# mux-board.net
KiCad netlist of a schematic drawn in EAGLE
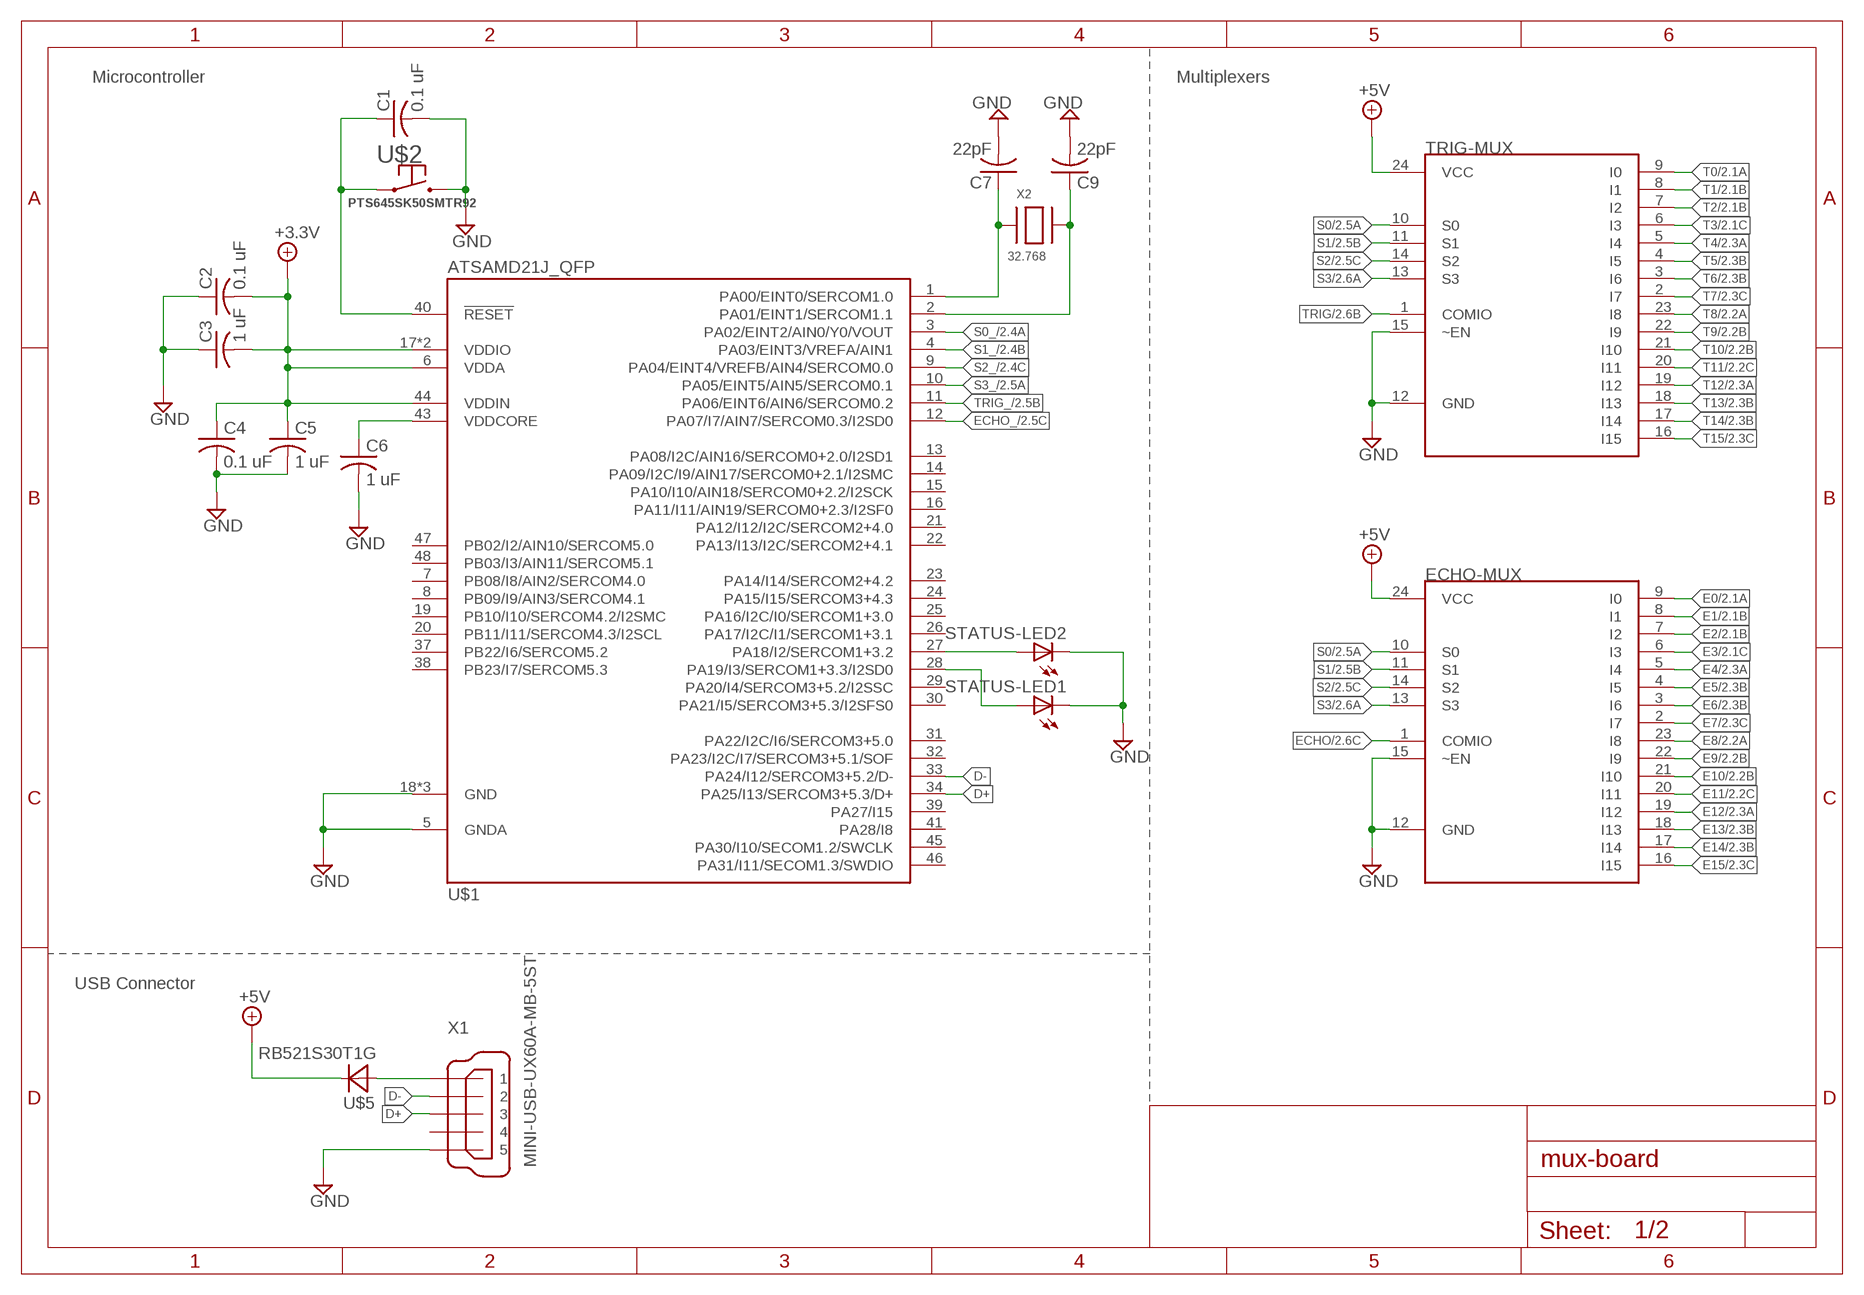
[diagram p0: schematic, sheet 1]
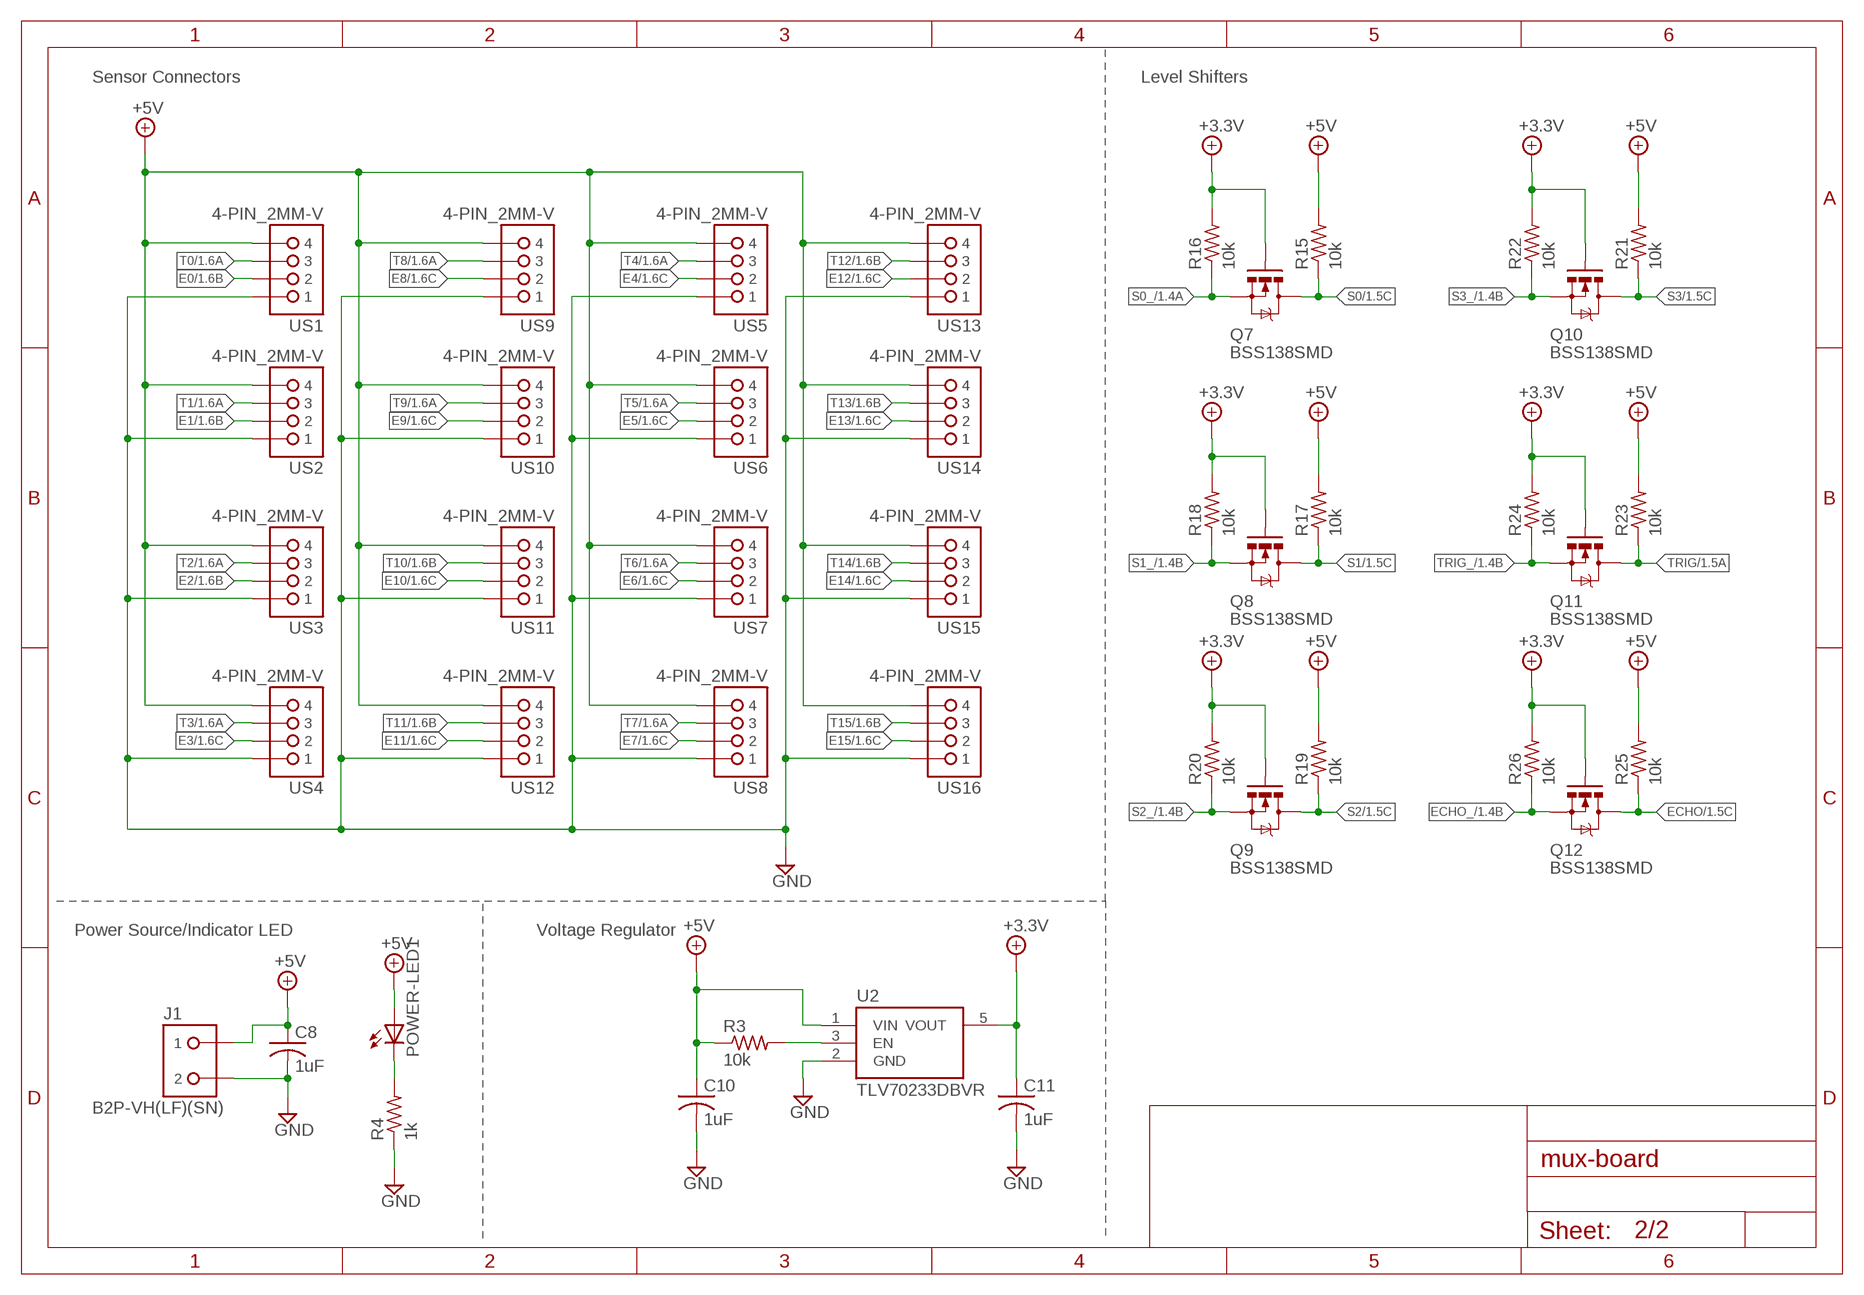
[diagram p1: schematic, sheet 2]

(export (version "E")
  (design (tool "Eeschema 10.0.6"))
  (components
    (comp (ref "C8")
      (value "1uF")
      (footprint "eagle-import:C0603")
      (libsource (lib "eagle-import") (part "C-USC0603"))
    )
    (comp (ref "C10")
      (value "1uF")
      (footprint "eagle-import:C0603")
      (libsource (lib "eagle-import") (part "C-USC0603"))
    )
    (comp (ref "C11")
      (value "1uF")
      (footprint "eagle-import:C0603")
      (libsource (lib "eagle-import") (part "C-USC0603"))
    )
    (comp (ref "J1")
      (value "B2P-VH(LF)(SN)")
      (footprint "eagle-import:B2P")
      (libsource (lib "eagle-import") (part "B2P?-VH(LF)(SN)"))
    )
    (comp (ref "POWER-LED1")
      (value "LEDSML0603")
      (footprint "eagle-import:SML0603")
      (libsource (lib "eagle-import") (part "LEDSML0603"))
    )
    (comp (ref "Q7")
      (value "BSS138SMD")
      (footprint "eagle-import:SPARKFUN_SOT23-3")
      (libsource (lib "eagle-import") (part "BSS138SMD"))
    )
    (comp (ref "Q8")
      (value "BSS138SMD")
      (footprint "eagle-import:SPARKFUN_SOT23-3")
      (libsource (lib "eagle-import") (part "BSS138SMD"))
    )
    (comp (ref "Q9")
      (value "BSS138SMD")
      (footprint "eagle-import:SPARKFUN_SOT23-3")
      (libsource (lib "eagle-import") (part "BSS138SMD"))
    )
    (comp (ref "Q10")
      (value "BSS138SMD")
      (footprint "eagle-import:SPARKFUN_SOT23-3")
      (libsource (lib "eagle-import") (part "BSS138SMD"))
    )
    (comp (ref "Q11")
      (value "BSS138SMD")
      (footprint "eagle-import:SPARKFUN_SOT23-3")
      (libsource (lib "eagle-import") (part "BSS138SMD"))
    )
    (comp (ref "Q12")
      (value "BSS138SMD")
      (footprint "eagle-import:SPARKFUN_SOT23-3")
      (libsource (lib "eagle-import") (part "BSS138SMD"))
    )
    (comp (ref "R3")
      (value "10k")
      (footprint "eagle-import:R0603")
      (libsource (lib "eagle-import") (part "resistor_348_R-US_R0603"))
    )
    (comp (ref "R4")
      (value "1k")
      (footprint "eagle-import:R0603")
      (libsource (lib "eagle-import") (part "resistor_348_R-US_R0603"))
    )
    (comp (ref "R15")
      (value "10k")
      (footprint "eagle-import:R0603")
      (libsource (lib "eagle-import") (part "R-US_R0603"))
    )
    (comp (ref "R16")
      (value "10k")
      (footprint "eagle-import:R0603")
      (libsource (lib "eagle-import") (part "R-US_R0603"))
    )
    (comp (ref "R17")
      (value "10k")
      (footprint "eagle-import:R0603")
      (libsource (lib "eagle-import") (part "R-US_R0603"))
    )
    (comp (ref "R18")
      (value "10k")
      (footprint "eagle-import:R0603")
      (libsource (lib "eagle-import") (part "R-US_R0603"))
    )
    (comp (ref "R19")
      (value "10k")
      (footprint "eagle-import:R0603")
      (libsource (lib "eagle-import") (part "R-US_R0603"))
    )
    (comp (ref "R20")
      (value "10k")
      (footprint "eagle-import:R0603")
      (libsource (lib "eagle-import") (part "R-US_R0603"))
    )
    (comp (ref "R21")
      (value "10k")
      (footprint "eagle-import:R0603")
      (libsource (lib "eagle-import") (part "R-US_R0603"))
    )
    (comp (ref "R22")
      (value "10k")
      (footprint "eagle-import:R0603")
      (libsource (lib "eagle-import") (part "R-US_R0603"))
    )
    (comp (ref "R23")
      (value "10k")
      (footprint "eagle-import:R0603")
      (libsource (lib "eagle-import") (part "R-US_R0603"))
    )
    (comp (ref "R24")
      (value "10k")
      (footprint "eagle-import:R0603")
      (libsource (lib "eagle-import") (part "R-US_R0603"))
    )
    (comp (ref "R25")
      (value "10k")
      (footprint "eagle-import:R0603")
      (libsource (lib "eagle-import") (part "R-US_R0603"))
    )
    (comp (ref "R26")
      (value "10k")
      (footprint "eagle-import:R0603")
      (libsource (lib "eagle-import") (part "R-US_R0603"))
    )
    (comp (ref "U2")
      (value "TLV70233DBVR")
      (footprint "eagle-import:SOT-23-5")
      (libsource (lib "eagle-import") (part "TLV70233DBVR"))
    )
    (comp (ref "US1")
      (value "4-PIN_2MM-V")
      (footprint "eagle-import:2MM-4-V")
      (libsource (lib "eagle-import") (part "4-PIN_2MM-V"))
    )
    (comp (ref "US2")
      (value "4-PIN_2MM-V")
      (footprint "eagle-import:2MM-4-V")
      (libsource (lib "eagle-import") (part "4-PIN_2MM-V"))
    )
    (comp (ref "US3")
      (value "4-PIN_2MM-V")
      (footprint "eagle-import:2MM-4-V")
      (libsource (lib "eagle-import") (part "4-PIN_2MM-V"))
    )
    (comp (ref "US4")
      (value "4-PIN_2MM-V")
      (footprint "eagle-import:2MM-4-V")
      (libsource (lib "eagle-import") (part "4-PIN_2MM-V"))
    )
    (comp (ref "US5")
      (value "4-PIN_2MM-V")
      (footprint "eagle-import:2MM-4-V")
      (libsource (lib "eagle-import") (part "4-PIN_2MM-V"))
    )
    (comp (ref "US6")
      (value "4-PIN_2MM-V")
      (footprint "eagle-import:2MM-4-V")
      (libsource (lib "eagle-import") (part "4-PIN_2MM-V"))
    )
    (comp (ref "US7")
      (value "4-PIN_2MM-V")
      (footprint "eagle-import:2MM-4-V")
      (libsource (lib "eagle-import") (part "4-PIN_2MM-V"))
    )
    (comp (ref "US8")
      (value "4-PIN_2MM-V")
      (footprint "eagle-import:2MM-4-V")
      (libsource (lib "eagle-import") (part "4-PIN_2MM-V"))
    )
    (comp (ref "US9")
      (value "4-PIN_2MM-V")
      (footprint "eagle-import:2MM-4-V")
      (libsource (lib "eagle-import") (part "4-PIN_2MM-V"))
    )
    (comp (ref "US10")
      (value "4-PIN_2MM-V")
      (footprint "eagle-import:2MM-4-V")
      (libsource (lib "eagle-import") (part "4-PIN_2MM-V"))
    )
    (comp (ref "US11")
      (value "4-PIN_2MM-V")
      (footprint "eagle-import:2MM-4-V")
      (libsource (lib "eagle-import") (part "4-PIN_2MM-V"))
    )
    (comp (ref "US12")
      (value "4-PIN_2MM-V")
      (footprint "eagle-import:2MM-4-V")
      (libsource (lib "eagle-import") (part "4-PIN_2MM-V"))
    )
    (comp (ref "US13")
      (value "4-PIN_2MM-V")
      (footprint "eagle-import:2MM-4-V")
      (libsource (lib "eagle-import") (part "4-PIN_2MM-V"))
    )
    (comp (ref "US14")
      (value "4-PIN_2MM-V")
      (footprint "eagle-import:2MM-4-V")
      (libsource (lib "eagle-import") (part "4-PIN_2MM-V"))
    )
    (comp (ref "US15")
      (value "4-PIN_2MM-V")
      (footprint "eagle-import:2MM-4-V")
      (libsource (lib "eagle-import") (part "4-PIN_2MM-V"))
    )
    (comp (ref "US16")
      (value "4-PIN_2MM-V")
      (footprint "eagle-import:2MM-4-V")
      (libsource (lib "eagle-import") (part "4-PIN_2MM-V"))
    )
    (comp (ref "C1")
      (value "0.1 uF")
      (footprint "eagle-import:C0603")
      (libsource (lib "eagle-import") (part "resistor_348_C-USC0603"))
    )
    (comp (ref "C2")
      (value "0.1 uF")
      (footprint "eagle-import:C0603")
      (libsource (lib "eagle-import") (part "resistor_348_C-USC0603"))
    )
    (comp (ref "C3")
      (value "1 uF")
      (footprint "eagle-import:C0603")
      (libsource (lib "eagle-import") (part "resistor_348_C-USC0603"))
    )
    (comp (ref "C4")
      (value "0.1 uF")
      (footprint "eagle-import:C0603")
      (libsource (lib "eagle-import") (part "resistor_348_C-USC0603"))
    )
    (comp (ref "C5")
      (value "1 uF")
      (footprint "eagle-import:C0603")
      (libsource (lib "eagle-import") (part "resistor_348_C-USC0603"))
    )
    (comp (ref "C6")
      (value "1 uF")
      (footprint "eagle-import:C0603")
      (libsource (lib "eagle-import") (part "resistor_348_C-USC0603"))
    )
    (comp (ref "C7")
      (value "22pF")
      (footprint "eagle-import:C0603")
      (libsource (lib "eagle-import") (part "C-USC0603"))
    )
    (comp (ref "C9")
      (value "22pF")
      (footprint "eagle-import:C0603")
      (libsource (lib "eagle-import") (part "C-USC0603"))
    )
    (comp (ref "ECHO-MUX")
      (value "CD74HC4067")
      (footprint "eagle-import:SO24R")
      (libsource (lib "eagle-import") (part "CD74HC4067"))
    )
    (comp (ref "STATUS-LED1")
      (value "LEDSML0603")
      (footprint "eagle-import:SML0603")
      (libsource (lib "eagle-import") (part "LEDSML0603"))
    )
    (comp (ref "STATUS-LED2")
      (value "LEDSML0603")
      (footprint "eagle-import:SML0603")
      (libsource (lib "eagle-import") (part "LEDSML0603"))
    )
    (comp (ref "TRIG-MUX")
      (value "CD74HC4067")
      (footprint "eagle-import:SO24R")
      (libsource (lib "eagle-import") (part "CD74HC4067"))
    )
    (comp (ref "U$1")
      (value "ATSAMD21J_QFP")
      (footprint "eagle-import:TQFP48_7MM")
      (libsource (lib "eagle-import") (part "ATSAMD21J_QFP"))
    )
    (comp (ref "U$2")
      (value "PTS645SK50SMTR92")
      (footprint "eagle-import:PTS645SK50SMTR92")
      (libsource (lib "eagle-import") (part "PTS645SK50SMTR92"))
    )
    (comp (ref "U$5")
      (value "RB521S30T1G")
      (footprint "eagle-import:SOD523")
      (libsource (lib "eagle-import") (part "RB521S30T1G"))
    )
    (comp (ref "X1")
      (value "MINI-USB-UX60A-MB-5ST")
      (footprint "eagle-import:UX60A-MB-5ST")
      (libsource (lib "eagle-import") (part "MINI-USB-UX60A-MB-5ST"))
    )
    (comp (ref "X2")
      (value "32.768")
      (footprint "eagle-import:XTAL3215")
      (libsource (lib "eagle-import") (part "XTAL-3.2X1.5"))
    )
  )
  (nets
    (net (code "1") (name "+3.3V") (class "Default")
      (node (ref "C11") (pin "1") (pinfunction "1_1") (pintype "passive"))
      (node (ref "C2") (pin "2") (pinfunction "2_2") (pintype "passive"))
      (node (ref "C3") (pin "2") (pinfunction "2_2") (pintype "passive"))
      (node (ref "C4") (pin "1") (pinfunction "1_1") (pintype "passive"))
      (node (ref "C5") (pin "1") (pinfunction "1_1") (pintype "passive"))
      (node (ref "Q10") (pin "1") (pinfunction "G_1") (pintype "passive"))
      (node (ref "Q11") (pin "1") (pinfunction "G_1") (pintype "passive"))
      (node (ref "Q12") (pin "1") (pinfunction "G_1") (pintype "passive"))
      (node (ref "Q7") (pin "1") (pinfunction "G_1") (pintype "passive"))
      (node (ref "Q8") (pin "1") (pinfunction "G_1") (pintype "passive"))
      (node (ref "Q9") (pin "1") (pinfunction "G_1") (pintype "passive"))
      (node (ref "R16") (pin "2") (pinfunction "2_2") (pintype "passive"))
      (node (ref "R18") (pin "2") (pinfunction "2_2") (pintype "passive"))
      (node (ref "R20") (pin "2") (pinfunction "2_2") (pintype "passive"))
      (node (ref "R22") (pin "2") (pinfunction "2_2") (pintype "passive"))
      (node (ref "R24") (pin "2") (pinfunction "2_2") (pintype "passive"))
      (node (ref "R26") (pin "2") (pinfunction "2_2") (pintype "passive"))
      (node (ref "U$1") (pin "17") (pinfunction "VDDIO_17") (pintype "power_in"))
      (node (ref "U$1") (pin "36") (pinfunction "VDDIO_36") (pintype "power_in"))
      (node (ref "U$1") (pin "44") (pinfunction "VDDIN_44") (pintype "power_in"))
      (node (ref "U$1") (pin "6") (pinfunction "VDDA_6") (pintype "power_in"))
      (node (ref "U2") (pin "5") (pinfunction "VOUT_5") (pintype "bidirectional"))
    )
    (net (code "2") (name "+5V") (class "Default")
      (node (ref "C10") (pin "1") (pinfunction "1_1") (pintype "passive"))
      (node (ref "C8") (pin "1") (pinfunction "1_1") (pintype "passive"))
      (node (ref "ECHO-MUX") (pin "24") (pinfunction "VCC_24") (pintype "bidirectional"))
      (node (ref "J1") (pin "1") (pinfunction "1_1") (pintype "bidirectional"))
      (node (ref "POWER-LED1") (pin "A") (pinfunction "A_A") (pintype "passive"))
      (node (ref "R15") (pin "2") (pinfunction "2_2") (pintype "passive"))
      (node (ref "R17") (pin "2") (pinfunction "2_2") (pintype "passive"))
      (node (ref "R19") (pin "2") (pinfunction "2_2") (pintype "passive"))
      (node (ref "R21") (pin "2") (pinfunction "2_2") (pintype "passive"))
      (node (ref "R23") (pin "2") (pinfunction "2_2") (pintype "passive"))
      (node (ref "R25") (pin "2") (pinfunction "2_2") (pintype "passive"))
      (node (ref "R3") (pin "1") (pinfunction "1_1") (pintype "passive"))
      (node (ref "TRIG-MUX") (pin "24") (pinfunction "VCC_24") (pintype "bidirectional"))
      (node (ref "U$5") (pin "C") (pinfunction "C_C") (pintype "passive"))
      (node (ref "U2") (pin "1") (pinfunction "VIN_1") (pintype "bidirectional"))
      (node (ref "US1") (pin "4") (pinfunction "4_4") (pintype "passive"))
      (node (ref "US10") (pin "4") (pinfunction "4_4") (pintype "passive"))
      (node (ref "US11") (pin "4") (pinfunction "4_4") (pintype "passive"))
      (node (ref "US12") (pin "4") (pinfunction "4_4") (pintype "passive"))
      (node (ref "US13") (pin "4") (pinfunction "4_4") (pintype "passive"))
      (node (ref "US14") (pin "4") (pinfunction "4_4") (pintype "passive"))
      (node (ref "US15") (pin "4") (pinfunction "4_4") (pintype "passive"))
      (node (ref "US16") (pin "4") (pinfunction "4_4") (pintype "passive"))
      (node (ref "US2") (pin "4") (pinfunction "4_4") (pintype "passive"))
      (node (ref "US3") (pin "4") (pinfunction "4_4") (pintype "passive"))
      (node (ref "US4") (pin "4") (pinfunction "4_4") (pintype "passive"))
      (node (ref "US5") (pin "4") (pinfunction "4_4") (pintype "passive"))
      (node (ref "US6") (pin "4") (pinfunction "4_4") (pintype "passive"))
      (node (ref "US7") (pin "4") (pinfunction "4_4") (pintype "passive"))
      (node (ref "US8") (pin "4") (pinfunction "4_4") (pintype "passive"))
      (node (ref "US9") (pin "4") (pinfunction "4_4") (pintype "passive"))
    )
    (net (code "3") (name "D+") (class "Default")
      (node (ref "U$1") (pin "34") (pinfunction "PA25/I13/SERCOM3+5.3/D+_34") (pintype "bidirectional"))
      (node (ref "X1") (pin "3") (pinfunction "3_3") (pintype "input"))
    )
    (net (code "4") (name "D-") (class "Default")
      (node (ref "U$1") (pin "33") (pinfunction "PA24/I12/SERCOM3+5.2/D-_33") (pintype "bidirectional"))
      (node (ref "X1") (pin "2") (pinfunction "2_2") (pintype "input"))
    )
    (net (code "5") (name "E0") (class "Default")
      (node (ref "ECHO-MUX") (pin "9") (pinfunction "I0_9") (pintype "bidirectional"))
      (node (ref "US1") (pin "2") (pinfunction "2_2") (pintype "passive"))
    )
    (net (code "6") (name "E1") (class "Default")
      (node (ref "ECHO-MUX") (pin "8") (pinfunction "I1_8") (pintype "bidirectional"))
      (node (ref "US2") (pin "2") (pinfunction "2_2") (pintype "passive"))
    )
    (net (code "7") (name "E2") (class "Default")
      (node (ref "ECHO-MUX") (pin "7") (pinfunction "I2_7") (pintype "bidirectional"))
      (node (ref "US3") (pin "2") (pinfunction "2_2") (pintype "passive"))
    )
    (net (code "8") (name "E3") (class "Default")
      (node (ref "ECHO-MUX") (pin "6") (pinfunction "I3_6") (pintype "bidirectional"))
      (node (ref "US4") (pin "2") (pinfunction "2_2") (pintype "passive"))
    )
    (net (code "9") (name "E4") (class "Default")
      (node (ref "ECHO-MUX") (pin "5") (pinfunction "I4_5") (pintype "bidirectional"))
      (node (ref "US5") (pin "2") (pinfunction "2_2") (pintype "passive"))
    )
    (net (code "10") (name "E5") (class "Default")
      (node (ref "ECHO-MUX") (pin "4") (pinfunction "I5_4") (pintype "bidirectional"))
      (node (ref "US6") (pin "2") (pinfunction "2_2") (pintype "passive"))
    )
    (net (code "11") (name "E6") (class "Default")
      (node (ref "ECHO-MUX") (pin "3") (pinfunction "I6_3") (pintype "bidirectional"))
      (node (ref "US7") (pin "2") (pinfunction "2_2") (pintype "passive"))
    )
    (net (code "12") (name "E7") (class "Default")
      (node (ref "ECHO-MUX") (pin "2") (pinfunction "I7_2") (pintype "bidirectional"))
      (node (ref "US8") (pin "2") (pinfunction "2_2") (pintype "passive"))
    )
    (net (code "13") (name "E8") (class "Default")
      (node (ref "ECHO-MUX") (pin "23") (pinfunction "I8_23") (pintype "bidirectional"))
      (node (ref "US9") (pin "2") (pinfunction "2_2") (pintype "passive"))
    )
    (net (code "14") (name "E9") (class "Default")
      (node (ref "ECHO-MUX") (pin "22") (pinfunction "I9_22") (pintype "bidirectional"))
      (node (ref "US10") (pin "2") (pinfunction "2_2") (pintype "passive"))
    )
    (net (code "15") (name "E10") (class "Default")
      (node (ref "ECHO-MUX") (pin "21") (pinfunction "I10_21") (pintype "bidirectional"))
      (node (ref "US11") (pin "2") (pinfunction "2_2") (pintype "passive"))
    )
    (net (code "16") (name "E11") (class "Default")
      (node (ref "ECHO-MUX") (pin "20") (pinfunction "I11_20") (pintype "bidirectional"))
      (node (ref "US12") (pin "2") (pinfunction "2_2") (pintype "passive"))
    )
    (net (code "17") (name "E12") (class "Default")
      (node (ref "ECHO-MUX") (pin "19") (pinfunction "I12_19") (pintype "bidirectional"))
      (node (ref "US13") (pin "2") (pinfunction "2_2") (pintype "passive"))
    )
    (net (code "18") (name "E13") (class "Default")
      (node (ref "ECHO-MUX") (pin "18") (pinfunction "I13_18") (pintype "bidirectional"))
      (node (ref "US14") (pin "2") (pinfunction "2_2") (pintype "passive"))
    )
    (net (code "19") (name "E14") (class "Default")
      (node (ref "ECHO-MUX") (pin "17") (pinfunction "I14_17") (pintype "bidirectional"))
      (node (ref "US15") (pin "2") (pinfunction "2_2") (pintype "passive"))
    )
    (net (code "20") (name "E15") (class "Default")
      (node (ref "ECHO-MUX") (pin "16") (pinfunction "I15_16") (pintype "bidirectional"))
      (node (ref "US16") (pin "2") (pinfunction "2_2") (pintype "passive"))
    )
    (net (code "21") (name "ECHO") (class "Default")
      (node (ref "ECHO-MUX") (pin "1") (pinfunction "COMIO_1") (pintype "bidirectional"))
      (node (ref "Q12") (pin "3") (pinfunction "D_3") (pintype "passive"))
      (node (ref "R25") (pin "1") (pinfunction "1_1") (pintype "passive"))
    )
    (net (code "22") (name "ECHO_") (class "Default")
      (node (ref "Q12") (pin "2") (pinfunction "S_2") (pintype "passive"))
      (node (ref "R26") (pin "1") (pinfunction "1_1") (pintype "passive"))
      (node (ref "U$1") (pin "12") (pinfunction "PA07/I7/AIN7/SERCOM0.3/I2SD0_12") (pintype "bidirectional"))
    )
    (net (code "23") (name "GND") (class "Default")
      (node (ref "C1") (pin "2") (pinfunction "2_2") (pintype "passive"))
      (node (ref "C10") (pin "2") (pinfunction "2_2") (pintype "passive"))
      (node (ref "C11") (pin "2") (pinfunction "2_2") (pintype "passive"))
      (node (ref "C2") (pin "1") (pinfunction "1_1") (pintype "passive"))
      (node (ref "C3") (pin "1") (pinfunction "1_1") (pintype "passive"))
      (node (ref "C4") (pin "2") (pinfunction "2_2") (pintype "passive"))
      (node (ref "C5") (pin "2") (pinfunction "2_2") (pintype "passive"))
      (node (ref "C6") (pin "2") (pinfunction "2_2") (pintype "passive"))
      (node (ref "C7") (pin "2") (pinfunction "2_2") (pintype "passive"))
      (node (ref "C8") (pin "2") (pinfunction "2_2") (pintype "passive"))
      (node (ref "C9") (pin "2") (pinfunction "2_2") (pintype "passive"))
      (node (ref "ECHO-MUX") (pin "12") (pinfunction "GND_12") (pintype "bidirectional"))
      (node (ref "ECHO-MUX") (pin "15") (pinfunction "~{EN}_15") (pintype "bidirectional"))
      (node (ref "J1") (pin "2") (pinfunction "2_2") (pintype "bidirectional"))
      (node (ref "R4") (pin "1") (pinfunction "1_1") (pintype "passive"))
      (node (ref "STATUS-LED1") (pin "C") (pinfunction "C_C") (pintype "passive"))
      (node (ref "STATUS-LED2") (pin "C") (pinfunction "C_C") (pintype "passive"))
      (node (ref "TRIG-MUX") (pin "12") (pinfunction "GND_12") (pintype "bidirectional"))
      (node (ref "TRIG-MUX") (pin "15") (pinfunction "~{EN}_15") (pintype "bidirectional"))
      (node (ref "U$1") (pin "18") (pinfunction "GND_18") (pintype "power_in"))
      (node (ref "U$1") (pin "35") (pinfunction "GND_35") (pintype "power_in"))
      (node (ref "U$1") (pin "42") (pinfunction "GND_42") (pintype "power_in"))
      (node (ref "U$1") (pin "5") (pinfunction "GNDA_5") (pintype "power_in"))
      (node (ref "U$2") (pin "3") (pinfunction "2_3") (pintype "passive"))
      (node (ref "U$2") (pin "4") (pinfunction "2_4") (pintype "passive"))
      (node (ref "U2") (pin "2") (pinfunction "GND_2") (pintype "bidirectional"))
      (node (ref "US1") (pin "1") (pinfunction "1_1") (pintype "passive"))
      (node (ref "US10") (pin "1") (pinfunction "1_1") (pintype "passive"))
      (node (ref "US11") (pin "1") (pinfunction "1_1") (pintype "passive"))
      (node (ref "US12") (pin "1") (pinfunction "1_1") (pintype "passive"))
      (node (ref "US13") (pin "1") (pinfunction "1_1") (pintype "passive"))
      (node (ref "US14") (pin "1") (pinfunction "1_1") (pintype "passive"))
      (node (ref "US15") (pin "1") (pinfunction "1_1") (pintype "passive"))
      (node (ref "US16") (pin "1") (pinfunction "1_1") (pintype "passive"))
      (node (ref "US2") (pin "1") (pinfunction "1_1") (pintype "passive"))
      (node (ref "US3") (pin "1") (pinfunction "1_1") (pintype "passive"))
      (node (ref "US4") (pin "1") (pinfunction "1_1") (pintype "passive"))
      (node (ref "US5") (pin "1") (pinfunction "1_1") (pintype "passive"))
      (node (ref "US6") (pin "1") (pinfunction "1_1") (pintype "passive"))
      (node (ref "US7") (pin "1") (pinfunction "1_1") (pintype "passive"))
      (node (ref "US8") (pin "1") (pinfunction "1_1") (pintype "passive"))
      (node (ref "US9") (pin "1") (pinfunction "1_1") (pintype "passive"))
      (node (ref "X1") (pin "5") (pinfunction "5_5") (pintype "input"))
    )
    (net (code "24") (name "Net-(POWER-LED1-PadC)") (class "Default")
      (node (ref "POWER-LED1") (pin "C") (pinfunction "C_C") (pintype "passive"))
      (node (ref "R4") (pin "2") (pinfunction "2_2") (pintype "passive"))
    )
    (net (code "25") (name "Net-(U$1-PA00{slash}EINT0{slash}SERCOM1.0)") (class "Default")
      (node (ref "C7") (pin "1") (pinfunction "1_1") (pintype "passive"))
      (node (ref "U$1") (pin "1") (pinfunction "PA00/EINT0/SERCOM1.0_1") (pintype "bidirectional"))
      (node (ref "X2") (pin "P$1") (pinfunction "P$1_P$1") (pintype "bidirectional"))
    )
    (net (code "26") (name "Net-(U$1-PA01{slash}EINT1{slash}SERCOM1.1)") (class "Default")
      (node (ref "C9") (pin "1") (pinfunction "1_1") (pintype "passive"))
      (node (ref "U$1") (pin "2") (pinfunction "PA01/EINT1/SERCOM1.1_2") (pintype "bidirectional"))
      (node (ref "X2") (pin "P$2") (pinfunction "P$2_P$2") (pintype "bidirectional"))
    )
    (net (code "27") (name "Net-(U$1-PA18{slash}I2{slash}SERCOM1+3.2)") (class "Default")
      (node (ref "STATUS-LED2") (pin "A") (pinfunction "A_A") (pintype "passive"))
      (node (ref "U$1") (pin "27") (pinfunction "PA18/I2/SERCOM1+3.2_27") (pintype "bidirectional"))
    )
    (net (code "28") (name "Net-(U$1-PA19{slash}I3{slash}SERCOM1+3.3{slash}I2SD0)") (class "Default")
      (node (ref "STATUS-LED1") (pin "A") (pinfunction "A_A") (pintype "passive"))
      (node (ref "U$1") (pin "28") (pinfunction "PA19/I3/SERCOM1+3.3/I2SD0_28") (pintype "bidirectional"))
    )
    (net (code "29") (name "Net-(U$1-VDDCORE)") (class "Default")
      (node (ref "C6") (pin "1") (pinfunction "1_1") (pintype "passive"))
      (node (ref "U$1") (pin "43") (pinfunction "VDDCORE_43") (pintype "power_in"))
    )
    (net (code "30") (name "Net-(U$1-~{RESET})") (class "Default")
      (node (ref "C1") (pin "1") (pinfunction "1_1") (pintype "passive"))
      (node (ref "U$1") (pin "40") (pinfunction "~{RESET}_40") (pintype "bidirectional"))
      (node (ref "U$2") (pin "1") (pinfunction "1_1") (pintype "passive"))
      (node (ref "U$2") (pin "2") (pinfunction "1_2") (pintype "passive"))
    )
    (net (code "31") (name "Net-(U$5-PadA)") (class "Default")
      (node (ref "U$5") (pin "A") (pinfunction "A_A") (pintype "passive"))
      (node (ref "X1") (pin "1") (pinfunction "1_1") (pintype "input"))
    )
    (net (code "32") (name "Net-(U2-EN)") (class "Default")
      (node (ref "R3") (pin "2") (pinfunction "2_2") (pintype "passive"))
      (node (ref "U2") (pin "3") (pinfunction "EN_3") (pintype "bidirectional"))
    )
    (net (code "33") (name "S0") (class "Default")
      (node (ref "ECHO-MUX") (pin "10") (pinfunction "S0_10") (pintype "bidirectional"))
      (node (ref "Q7") (pin "3") (pinfunction "D_3") (pintype "passive"))
      (node (ref "R15") (pin "1") (pinfunction "1_1") (pintype "passive"))
      (node (ref "TRIG-MUX") (pin "10") (pinfunction "S0_10") (pintype "bidirectional"))
    )
    (net (code "34") (name "S0_") (class "Default")
      (node (ref "Q7") (pin "2") (pinfunction "S_2") (pintype "passive"))
      (node (ref "R16") (pin "1") (pinfunction "1_1") (pintype "passive"))
      (node (ref "U$1") (pin "3") (pinfunction "PA02/EINT2/AIN0/Y0/VOUT_3") (pintype "bidirectional"))
    )
    (net (code "35") (name "S1") (class "Default")
      (node (ref "ECHO-MUX") (pin "11") (pinfunction "S1_11") (pintype "bidirectional"))
      (node (ref "Q8") (pin "3") (pinfunction "D_3") (pintype "passive"))
      (node (ref "R17") (pin "1") (pinfunction "1_1") (pintype "passive"))
      (node (ref "TRIG-MUX") (pin "11") (pinfunction "S1_11") (pintype "bidirectional"))
    )
    (net (code "36") (name "S1_") (class "Default")
      (node (ref "Q8") (pin "2") (pinfunction "S_2") (pintype "passive"))
      (node (ref "R18") (pin "1") (pinfunction "1_1") (pintype "passive"))
      (node (ref "U$1") (pin "4") (pinfunction "PA03/EINT3/VREFA/AIN1_4") (pintype "bidirectional"))
    )
    (net (code "37") (name "S2") (class "Default")
      (node (ref "ECHO-MUX") (pin "14") (pinfunction "S2_14") (pintype "bidirectional"))
      (node (ref "Q9") (pin "3") (pinfunction "D_3") (pintype "passive"))
      (node (ref "R19") (pin "1") (pinfunction "1_1") (pintype "passive"))
      (node (ref "TRIG-MUX") (pin "14") (pinfunction "S2_14") (pintype "bidirectional"))
    )
    (net (code "38") (name "S2_") (class "Default")
      (node (ref "Q9") (pin "2") (pinfunction "S_2") (pintype "passive"))
      (node (ref "R20") (pin "1") (pinfunction "1_1") (pintype "passive"))
      (node (ref "U$1") (pin "9") (pinfunction "PA04/EINT4/VREFB/AIN4/SERCOM0.0_9") (pintype "bidirectional"))
    )
    (net (code "39") (name "S3") (class "Default")
      (node (ref "ECHO-MUX") (pin "13") (pinfunction "S3_13") (pintype "bidirectional"))
      (node (ref "Q10") (pin "3") (pinfunction "D_3") (pintype "passive"))
      (node (ref "R21") (pin "1") (pinfunction "1_1") (pintype "passive"))
      (node (ref "TRIG-MUX") (pin "13") (pinfunction "S3_13") (pintype "bidirectional"))
    )
    (net (code "40") (name "S3_") (class "Default")
      (node (ref "Q10") (pin "2") (pinfunction "S_2") (pintype "passive"))
      (node (ref "R22") (pin "1") (pinfunction "1_1") (pintype "passive"))
      (node (ref "U$1") (pin "10") (pinfunction "PA05/EINT5/AIN5/SERCOM0.1_10") (pintype "bidirectional"))
    )
    (net (code "41") (name "T0") (class "Default")
      (node (ref "TRIG-MUX") (pin "9") (pinfunction "I0_9") (pintype "bidirectional"))
      (node (ref "US1") (pin "3") (pinfunction "3_3") (pintype "passive"))
    )
    (net (code "42") (name "T1") (class "Default")
      (node (ref "TRIG-MUX") (pin "8") (pinfunction "I1_8") (pintype "bidirectional"))
      (node (ref "US2") (pin "3") (pinfunction "3_3") (pintype "passive"))
    )
    (net (code "43") (name "T2") (class "Default")
      (node (ref "TRIG-MUX") (pin "7") (pinfunction "I2_7") (pintype "bidirectional"))
      (node (ref "US3") (pin "3") (pinfunction "3_3") (pintype "passive"))
    )
    (net (code "44") (name "T3") (class "Default")
      (node (ref "TRIG-MUX") (pin "6") (pinfunction "I3_6") (pintype "bidirectional"))
      (node (ref "US4") (pin "3") (pinfunction "3_3") (pintype "passive"))
    )
    (net (code "45") (name "T4") (class "Default")
      (node (ref "TRIG-MUX") (pin "5") (pinfunction "I4_5") (pintype "bidirectional"))
      (node (ref "US5") (pin "3") (pinfunction "3_3") (pintype "passive"))
    )
    (net (code "46") (name "T5") (class "Default")
      (node (ref "TRIG-MUX") (pin "4") (pinfunction "I5_4") (pintype "bidirectional"))
      (node (ref "US6") (pin "3") (pinfunction "3_3") (pintype "passive"))
    )
    (net (code "47") (name "T6") (class "Default")
      (node (ref "TRIG-MUX") (pin "3") (pinfunction "I6_3") (pintype "bidirectional"))
      (node (ref "US7") (pin "3") (pinfunction "3_3") (pintype "passive"))
    )
    (net (code "48") (name "T7") (class "Default")
      (node (ref "TRIG-MUX") (pin "2") (pinfunction "I7_2") (pintype "bidirectional"))
      (node (ref "US8") (pin "3") (pinfunction "3_3") (pintype "passive"))
    )
    (net (code "49") (name "T8") (class "Default")
      (node (ref "TRIG-MUX") (pin "23") (pinfunction "I8_23") (pintype "bidirectional"))
      (node (ref "US9") (pin "3") (pinfunction "3_3") (pintype "passive"))
    )
    (net (code "50") (name "T9") (class "Default")
      (node (ref "TRIG-MUX") (pin "22") (pinfunction "I9_22") (pintype "bidirectional"))
      (node (ref "US10") (pin "3") (pinfunction "3_3") (pintype "passive"))
    )
    (net (code "51") (name "T10") (class "Default")
      (node (ref "TRIG-MUX") (pin "21") (pinfunction "I10_21") (pintype "bidirectional"))
      (node (ref "US11") (pin "3") (pinfunction "3_3") (pintype "passive"))
    )
    (net (code "52") (name "T11") (class "Default")
      (node (ref "TRIG-MUX") (pin "20") (pinfunction "I11_20") (pintype "bidirectional"))
      (node (ref "US12") (pin "3") (pinfunction "3_3") (pintype "passive"))
    )
    (net (code "53") (name "T12") (class "Default")
      (node (ref "TRIG-MUX") (pin "19") (pinfunction "I12_19") (pintype "bidirectional"))
      (node (ref "US13") (pin "3") (pinfunction "3_3") (pintype "passive"))
    )
    (net (code "54") (name "T13") (class "Default")
      (node (ref "TRIG-MUX") (pin "18") (pinfunction "I13_18") (pintype "bidirectional"))
      (node (ref "US14") (pin "3") (pinfunction "3_3") (pintype "passive"))
    )
    (net (code "55") (name "T14") (class "Default")
      (node (ref "TRIG-MUX") (pin "17") (pinfunction "I14_17") (pintype "bidirectional"))
      (node (ref "US15") (pin "3") (pinfunction "3_3") (pintype "passive"))
    )
    (net (code "56") (name "T15") (class "Default")
      (node (ref "TRIG-MUX") (pin "16") (pinfunction "I15_16") (pintype "bidirectional"))
      (node (ref "US16") (pin "3") (pinfunction "3_3") (pintype "passive"))
    )
    (net (code "57") (name "TRIG") (class "Default")
      (node (ref "Q11") (pin "3") (pinfunction "D_3") (pintype "passive"))
      (node (ref "R23") (pin "1") (pinfunction "1_1") (pintype "passive"))
      (node (ref "TRIG-MUX") (pin "1") (pinfunction "COMIO_1") (pintype "bidirectional"))
    )
    (net (code "58") (name "TRIG_") (class "Default")
      (node (ref "Q11") (pin "2") (pinfunction "S_2") (pintype "passive"))
      (node (ref "R24") (pin "1") (pinfunction "1_1") (pintype "passive"))
      (node (ref "U$1") (pin "11") (pinfunction "PA06/EINT6/AIN6/SERCOM0.2_11") (pintype "bidirectional"))
    )
    (net (code "59") (name "unconnected-(U$1-PA08{slash}I2C{slash}AIN16{slash}SERCOM0+2.0{slash}I2SD1-Pad13)") (class "Default")
      (node (ref "U$1") (pin "13") (pinfunction "PA08/I2C/AIN16/SERCOM0+2.0/I2SD1_13") (pintype "bidirectional"))
    )
    (net (code "60") (name "unconnected-(U$1-PA09{slash}I2C{slash}I9{slash}AIN17{slash}SERCOM0+2.1{slash}I2SMC-Pad14)") (class "Default")
      (node (ref "U$1") (pin "14") (pinfunction "PA09/I2C/I9/AIN17/SERCOM0+2.1/I2SMC_14") (pintype "bidirectional"))
    )
    (net (code "61") (name "unconnected-(U$1-PA10{slash}I10{slash}AIN18{slash}SERCOM0+2.2{slash}I2SCK-Pad15)") (class "Default")
      (node (ref "U$1") (pin "15") (pinfunction "PA10/I10/AIN18/SERCOM0+2.2/I2SCK_15") (pintype "bidirectional"))
    )
    (net (code "62") (name "unconnected-(U$1-PA11{slash}I11{slash}AIN19{slash}SERCOM0+2.3{slash}I2SF0-Pad16)") (class "Default")
      (node (ref "U$1") (pin "16") (pinfunction "PA11/I11/AIN19/SERCOM0+2.3/I2SF0_16") (pintype "bidirectional"))
    )
    (net (code "63") (name "unconnected-(U$1-PA12{slash}I12{slash}I2C{slash}SERCOM2+4.0-Pad21)") (class "Default")
      (node (ref "U$1") (pin "21") (pinfunction "PA12/I12/I2C/SERCOM2+4.0_21") (pintype "bidirectional"))
    )
    (net (code "64") (name "unconnected-(U$1-PA13{slash}I13{slash}I2C{slash}SERCOM2+4.1-Pad22)") (class "Default")
      (node (ref "U$1") (pin "22") (pinfunction "PA13/I13/I2C/SERCOM2+4.1_22") (pintype "bidirectional"))
    )
    (net (code "65") (name "unconnected-(U$1-PA14{slash}I14{slash}SERCOM2+4.2-Pad23)") (class "Default")
      (node (ref "U$1") (pin "23") (pinfunction "PA14/I14/SERCOM2+4.2_23") (pintype "bidirectional"))
    )
    (net (code "66") (name "unconnected-(U$1-PA15{slash}I15{slash}SERCOM3+4.3-Pad24)") (class "Default")
      (node (ref "U$1") (pin "24") (pinfunction "PA15/I15/SERCOM3+4.3_24") (pintype "bidirectional"))
    )
    (net (code "67") (name "unconnected-(U$1-PA16{slash}I2C{slash}I0{slash}SERCOM1+3.0-Pad25)") (class "Default")
      (node (ref "U$1") (pin "25") (pinfunction "PA16/I2C/I0/SERCOM1+3.0_25") (pintype "bidirectional"))
    )
    (net (code "68") (name "unconnected-(U$1-PA17{slash}I2C{slash}I1{slash}SERCOM1+3.1-Pad26)") (class "Default")
      (node (ref "U$1") (pin "26") (pinfunction "PA17/I2C/I1/SERCOM1+3.1_26") (pintype "bidirectional"))
    )
    (net (code "69") (name "unconnected-(U$1-PA20{slash}I4{slash}SERCOM3+5.2{slash}I2SSC-Pad29)") (class "Default")
      (node (ref "U$1") (pin "29") (pinfunction "PA20/I4/SERCOM3+5.2/I2SSC_29") (pintype "bidirectional"))
    )
    (net (code "70") (name "unconnected-(U$1-PA21{slash}I5{slash}SERCOM3+5.3{slash}I2SFS0-Pad30)") (class "Default")
      (node (ref "U$1") (pin "30") (pinfunction "PA21/I5/SERCOM3+5.3/I2SFS0_30") (pintype "bidirectional"))
    )
    (net (code "71") (name "unconnected-(U$1-PA22{slash}I2C{slash}I6{slash}SERCOM3+5.0-Pad31)") (class "Default")
      (node (ref "U$1") (pin "31") (pinfunction "PA22/I2C/I6/SERCOM3+5.0_31") (pintype "bidirectional"))
    )
    (net (code "72") (name "unconnected-(U$1-PA23{slash}I2C{slash}I7{slash}SERCOM3+5.1{slash}SOF-Pad32)") (class "Default")
      (node (ref "U$1") (pin "32") (pinfunction "PA23/I2C/I7/SERCOM3+5.1/SOF_32") (pintype "bidirectional"))
    )
    (net (code "73") (name "unconnected-(U$1-PA27{slash}I15-Pad39)") (class "Default")
      (node (ref "U$1") (pin "39") (pinfunction "PA27/I15_39") (pintype "bidirectional"))
    )
    (net (code "74") (name "unconnected-(U$1-PA28{slash}I8-Pad41)") (class "Default")
      (node (ref "U$1") (pin "41") (pinfunction "PA28/I8_41") (pintype "bidirectional"))
    )
    (net (code "75") (name "unconnected-(U$1-PA30{slash}I10{slash}SECOM1.2{slash}SWCLK-Pad45)") (class "Default")
      (node (ref "U$1") (pin "45") (pinfunction "PA30/I10/SECOM1.2/SWCLK_45") (pintype "bidirectional"))
    )
    (net (code "76") (name "unconnected-(U$1-PA31{slash}I11{slash}SECOM1.3{slash}SWDIO-Pad46)") (class "Default")
      (node (ref "U$1") (pin "46") (pinfunction "PA31/I11/SECOM1.3/SWDIO_46") (pintype "bidirectional"))
    )
    (net (code "77") (name "unconnected-(U$1-PB02{slash}I2{slash}AIN10{slash}SERCOM5.0-Pad47)") (class "Default")
      (node (ref "U$1") (pin "47") (pinfunction "PB02/I2/AIN10/SERCOM5.0_47") (pintype "bidirectional"))
    )
    (net (code "78") (name "unconnected-(U$1-PB03{slash}I3{slash}AIN11{slash}SERCOM5.1-Pad48)") (class "Default")
      (node (ref "U$1") (pin "48") (pinfunction "PB03/I3/AIN11/SERCOM5.1_48") (pintype "bidirectional"))
    )
    (net (code "79") (name "unconnected-(U$1-PB08{slash}I8{slash}AIN2{slash}SERCOM4.0-Pad7)") (class "Default")
      (node (ref "U$1") (pin "7") (pinfunction "PB08/I8/AIN2/SERCOM4.0_7") (pintype "bidirectional"))
    )
    (net (code "80") (name "unconnected-(U$1-PB09{slash}I9{slash}AIN3{slash}SERCOM4.1-Pad8)") (class "Default")
      (node (ref "U$1") (pin "8") (pinfunction "PB09/I9/AIN3/SERCOM4.1_8") (pintype "bidirectional"))
    )
    (net (code "81") (name "unconnected-(U$1-PB10{slash}I10{slash}SERCOM4.2{slash}I2SMC-Pad19)") (class "Default")
      (node (ref "U$1") (pin "19") (pinfunction "PB10/I10/SERCOM4.2/I2SMC_19") (pintype "bidirectional"))
    )
    (net (code "82") (name "unconnected-(U$1-PB11{slash}I11{slash}SERCOM4.3{slash}I2SCL-Pad20)") (class "Default")
      (node (ref "U$1") (pin "20") (pinfunction "PB11/I11/SERCOM4.3/I2SCL_20") (pintype "bidirectional"))
    )
    (net (code "83") (name "unconnected-(U$1-PB22{slash}I6{slash}SERCOM5.2-Pad37)") (class "Default")
      (node (ref "U$1") (pin "37") (pinfunction "PB22/I6/SERCOM5.2_37") (pintype "bidirectional"))
    )
    (net (code "84") (name "unconnected-(U$1-PB23{slash}I7{slash}SERCOM5.3-Pad38)") (class "Default")
      (node (ref "U$1") (pin "38") (pinfunction "PB23/I7/SERCOM5.3_38") (pintype "bidirectional"))
    )
    (net (code "85") (name "unconnected-(X1-Pad4)") (class "Default")
      (node (ref "X1") (pin "4") (pinfunction "4_4") (pintype "input"))
    )
  )
)
